# SCH_SUB_BUTTON.net
KiCad netlist of a schematic drawn in Altium Designer
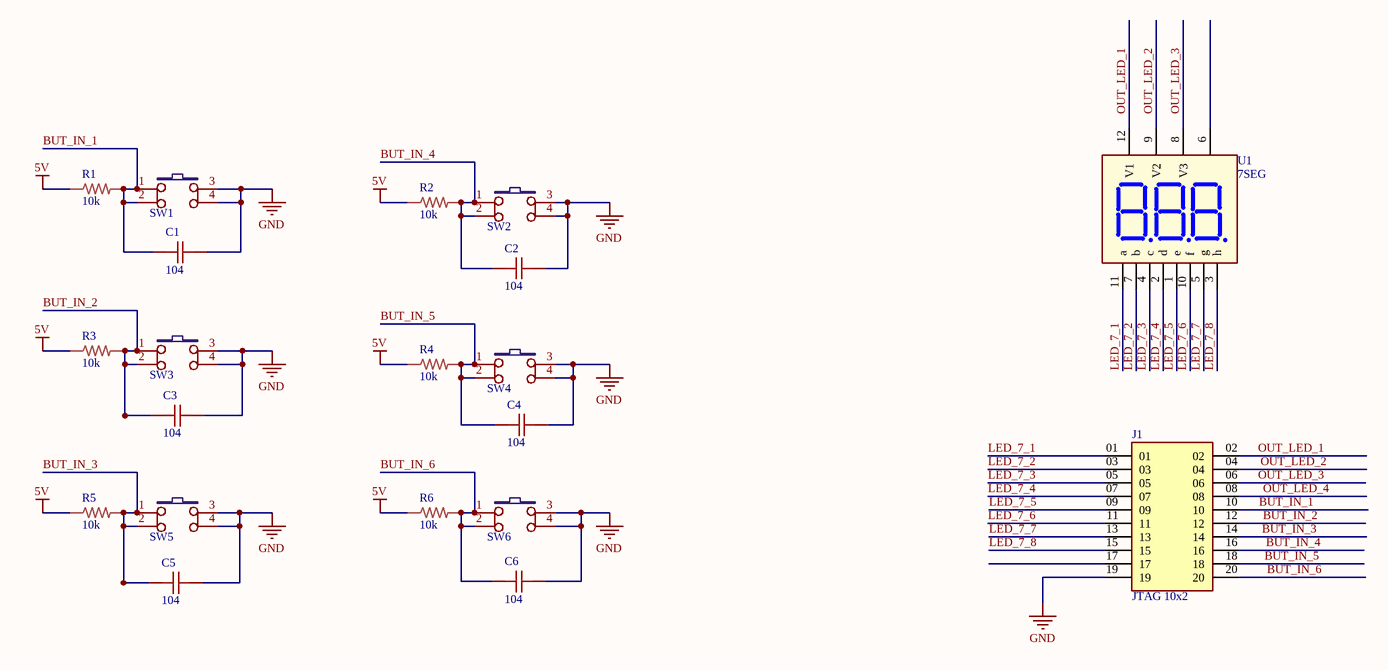
[diagram p0: SCH_SUB_BUTTON.SchDoc]

(export (version "E")
  (design (tool "Eeschema 10.0.6"))
  (components
    (comp (ref "C1")
      (value "104")
      (footprint "CAP_SMD_1206")
      (description "Cap SMD multiple types as 0402 0603 0805 1206")
      (fields (field (name "Comment") "Cap_SMD"))
      (libsource (lib "Integrated_Library_Kylin915") (part "Cap_SMD"))
    )
    (comp (ref "C2")
      (value "104")
      (footprint "CAP_SMD_1206")
      (description "Cap SMD multiple types as 0402 0603 0805 1206")
      (fields (field (name "Comment") "Cap_SMD"))
      (libsource (lib "Integrated_Library_Kylin915") (part "Cap_SMD"))
    )
    (comp (ref "C3")
      (value "104")
      (footprint "CAP_SMD_1206")
      (description "Cap SMD multiple types as 0402 0603 0805 1206")
      (fields (field (name "Comment") "Cap_SMD"))
      (libsource (lib "Integrated_Library_Kylin915") (part "Cap_SMD"))
    )
    (comp (ref "C4")
      (value "104")
      (footprint "CAP_SMD_1206")
      (description "Cap SMD multiple types as 0402 0603 0805 1206")
      (fields (field (name "Comment") "Cap_SMD"))
      (libsource (lib "Integrated_Library_Kylin915") (part "Cap_SMD"))
    )
    (comp (ref "C5")
      (value "104")
      (footprint "CAP_SMD_1206")
      (description "Cap SMD multiple types as 0402 0603 0805 1206")
      (fields (field (name "Comment") "Cap_SMD"))
      (libsource (lib "Integrated_Library_Kylin915") (part "Cap_SMD"))
    )
    (comp (ref "C6")
      (value "104")
      (footprint "CAP_SMD_1206")
      (description "Cap SMD multiple types as 0402 0603 0805 1206")
      (fields (field (name "Comment") "Cap_SMD"))
      (libsource (lib "Integrated_Library_Kylin915") (part "Cap_SMD"))
    )
    (comp (ref "J1")
      (value "JTAG 10x2")
      (footprint "JTAG")
      (description "Connector Header Through Hole 20 position 0.100 (2.54mm)")
      (fields (field (name "MP") "TSS-110-01-G-D") (field (name "MF") "Samtec"))
      (libsource (lib "library_principle_circuit_dang_nhien") (part "JTAG 10x2"))
    )
    (comp (ref "R1")
      (value "10k")
      (footprint "Res_SMD_1206")
      (description "res smd")
      (fields (field (name "Comment") "Res_SMD"))
      (libsource (lib "Integrated_Library_Kylin915") (part "Res_SMD"))
    )
    (comp (ref "R2")
      (value "10k")
      (footprint "Res_SMD_1206")
      (description "res smd")
      (fields (field (name "Comment") "Res_SMD"))
      (libsource (lib "Integrated_Library_Kylin915") (part "Res_SMD"))
    )
    (comp (ref "R3")
      (value "10k")
      (footprint "Res_SMD_1206")
      (description "res smd")
      (fields (field (name "Comment") "Res_SMD"))
      (libsource (lib "Integrated_Library_Kylin915") (part "Res_SMD"))
    )
    (comp (ref "R4")
      (value "10k")
      (footprint "Res_SMD_1206")
      (description "res smd")
      (fields (field (name "Comment") "Res_SMD"))
      (libsource (lib "Integrated_Library_Kylin915") (part "Res_SMD"))
    )
    (comp (ref "R5")
      (value "10k")
      (footprint "Res_SMD_1206")
      (description "res smd")
      (fields (field (name "Comment") "Res_SMD"))
      (libsource (lib "Integrated_Library_Kylin915") (part "Res_SMD"))
    )
    (comp (ref "R6")
      (value "10k")
      (footprint "Res_SMD_1206")
      (description "res smd")
      (fields (field (name "Comment") "Res_SMD"))
      (libsource (lib "Integrated_Library_Kylin915") (part "Res_SMD"))
    )
    (comp (ref "SW1")
      (value "Button6x6")
      (footprint "Button6x6smd")
      (description "button 6x6 mm")
      (libsource (lib "Integrated_Library_Kylin915") (part "Button6x6"))
    )
    (comp (ref "SW2")
      (value "Button6x6")
      (footprint "Button6x6smd")
      (description "button 6x6 mm")
      (libsource (lib "Integrated_Library_Kylin915") (part "Button6x6"))
    )
    (comp (ref "SW3")
      (value "Button6x6")
      (footprint "Button6x6smd")
      (description "button 6x6 mm")
      (libsource (lib "Integrated_Library_Kylin915") (part "Button6x6"))
    )
    (comp (ref "SW4")
      (value "Button6x6")
      (footprint "Button6x6smd")
      (description "button 6x6 mm")
      (libsource (lib "Integrated_Library_Kylin915") (part "Button6x6"))
    )
    (comp (ref "SW5")
      (value "Button6x6")
      (footprint "Button6x6smd")
      (description "button 6x6 mm")
      (libsource (lib "Integrated_Library_Kylin915") (part "Button6x6"))
    )
    (comp (ref "SW6")
      (value "Button6x6")
      (footprint "Button6x6smd")
      (description "button 6x6 mm")
      (libsource (lib "Integrated_Library_Kylin915") (part "Button6x6"))
    )
    (comp (ref "U1")
      (value "7SEG")
      (footprint "7SEG")
      (description "Three 7 Seg Dipslay")
      (libsource (lib "Integrated_Library_Kylin915") (part "LED 7SEG"))
    )
  )
  (nets
    (net (code "1") (name "/BUT_IN_1") (class "Default")
      (node (ref "C1") (pin "2") (pinfunction "2_2") (pintype "passive"))
      (node (ref "J1") (pin "10") (pinfunction "10_10") (pintype "passive"))
      (node (ref "R1") (pin "2") (pinfunction "2_2") (pintype "passive"))
      (node (ref "SW1") (pin "1") (pinfunction "1_1") (pintype "passive"))
      (node (ref "SW1") (pin "2") (pinfunction "2_2") (pintype "passive"))
    )
    (net (code "2") (name "/BUT_IN_2") (class "Default")
      (node (ref "C3") (pin "2") (pinfunction "2_2") (pintype "passive"))
      (node (ref "J1") (pin "12") (pinfunction "12_12") (pintype "passive"))
      (node (ref "R3") (pin "2") (pinfunction "2_2") (pintype "passive"))
      (node (ref "SW3") (pin "1") (pinfunction "1_1") (pintype "passive"))
      (node (ref "SW3") (pin "2") (pinfunction "2_2") (pintype "passive"))
    )
    (net (code "3") (name "/BUT_IN_3") (class "Default")
      (node (ref "C5") (pin "2") (pinfunction "2_2") (pintype "passive"))
      (node (ref "J1") (pin "14") (pinfunction "14_14") (pintype "passive"))
      (node (ref "R5") (pin "2") (pinfunction "2_2") (pintype "passive"))
      (node (ref "SW5") (pin "1") (pinfunction "1_1") (pintype "passive"))
      (node (ref "SW5") (pin "2") (pinfunction "2_2") (pintype "passive"))
    )
    (net (code "4") (name "/BUT_IN_4") (class "Default")
      (node (ref "C2") (pin "2") (pinfunction "2_2") (pintype "passive"))
      (node (ref "J1") (pin "16") (pinfunction "16_16") (pintype "passive"))
      (node (ref "R2") (pin "2") (pinfunction "2_2") (pintype "passive"))
      (node (ref "SW2") (pin "1") (pinfunction "1_1") (pintype "passive"))
      (node (ref "SW2") (pin "2") (pinfunction "2_2") (pintype "passive"))
    )
    (net (code "5") (name "/BUT_IN_5") (class "Default")
      (node (ref "C4") (pin "2") (pinfunction "2_2") (pintype "passive"))
      (node (ref "J1") (pin "18") (pinfunction "18_18") (pintype "passive"))
      (node (ref "R4") (pin "2") (pinfunction "2_2") (pintype "passive"))
      (node (ref "SW4") (pin "1") (pinfunction "1_1") (pintype "passive"))
      (node (ref "SW4") (pin "2") (pinfunction "2_2") (pintype "passive"))
    )
    (net (code "6") (name "/BUT_IN_6") (class "Default")
      (node (ref "C6") (pin "2") (pinfunction "2_2") (pintype "passive"))
      (node (ref "J1") (pin "20") (pinfunction "20_20") (pintype "passive"))
      (node (ref "R6") (pin "2") (pinfunction "2_2") (pintype "passive"))
      (node (ref "SW6") (pin "1") (pinfunction "1_1") (pintype "passive"))
      (node (ref "SW6") (pin "2") (pinfunction "2_2") (pintype "passive"))
    )
    (net (code "7") (name "/LED_7_1") (class "Default")
      (node (ref "J1") (pin "01") (pinfunction "01_01") (pintype "passive"))
      (node (ref "U1") (pin "11") (pinfunction "a_11") (pintype "passive"))
    )
    (net (code "8") (name "/LED_7_2") (class "Default")
      (node (ref "J1") (pin "03") (pinfunction "03_03") (pintype "passive"))
      (node (ref "U1") (pin "7") (pinfunction "b_7") (pintype "passive"))
    )
    (net (code "9") (name "/LED_7_3") (class "Default")
      (node (ref "J1") (pin "05") (pinfunction "05_05") (pintype "passive"))
      (node (ref "U1") (pin "4") (pinfunction "c_4") (pintype "passive"))
    )
    (net (code "10") (name "/LED_7_4") (class "Default")
      (node (ref "J1") (pin "07") (pinfunction "07_07") (pintype "passive"))
      (node (ref "U1") (pin "2") (pinfunction "d_2") (pintype "passive"))
    )
    (net (code "11") (name "/LED_7_5") (class "Default")
      (node (ref "J1") (pin "09") (pinfunction "09_09") (pintype "passive"))
      (node (ref "U1") (pin "1") (pinfunction "e_1") (pintype "passive"))
    )
    (net (code "12") (name "/LED_7_6") (class "Default")
      (node (ref "J1") (pin "11") (pinfunction "11_11") (pintype "passive"))
      (node (ref "U1") (pin "10") (pinfunction "f_10") (pintype "passive"))
    )
    (net (code "13") (name "/LED_7_7") (class "Default")
      (node (ref "J1") (pin "13") (pinfunction "13_13") (pintype "passive"))
      (node (ref "U1") (pin "5") (pinfunction "g_5") (pintype "passive"))
    )
    (net (code "14") (name "/LED_7_8") (class "Default")
      (node (ref "J1") (pin "15") (pinfunction "15_15") (pintype "passive"))
      (node (ref "U1") (pin "3") (pinfunction "h_3") (pintype "passive"))
    )
    (net (code "15") (name "/OUT_LED_1") (class "Default")
      (node (ref "J1") (pin "02") (pinfunction "02_02") (pintype "passive"))
      (node (ref "U1") (pin "12") (pinfunction "V1_12") (pintype "passive"))
    )
    (net (code "16") (name "/OUT_LED_2") (class "Default")
      (node (ref "J1") (pin "04") (pinfunction "04_04") (pintype "passive"))
      (node (ref "U1") (pin "9") (pinfunction "V2_9") (pintype "passive"))
    )
    (net (code "17") (name "/OUT_LED_3") (class "Default")
      (node (ref "J1") (pin "06") (pinfunction "06_06") (pintype "passive"))
      (node (ref "U1") (pin "8") (pinfunction "V3_8") (pintype "passive"))
    )
    (net (code "18") (name "/OUT_LED_4") (class "Default")
      (node (ref "J1") (pin "08") (pinfunction "08_08") (pintype "passive"))
    )
    (net (code "19") (name "5V") (class "Default")
      (node (ref "R1") (pin "1") (pinfunction "1_1") (pintype "passive"))
      (node (ref "R2") (pin "1") (pinfunction "1_1") (pintype "passive"))
      (node (ref "R3") (pin "1") (pinfunction "1_1") (pintype "passive"))
      (node (ref "R4") (pin "1") (pinfunction "1_1") (pintype "passive"))
      (node (ref "R5") (pin "1") (pinfunction "1_1") (pintype "passive"))
      (node (ref "R6") (pin "1") (pinfunction "1_1") (pintype "passive"))
    )
    (net (code "20") (name "GND") (class "Default")
      (node (ref "C1") (pin "1") (pinfunction "1_1") (pintype "passive"))
      (node (ref "C2") (pin "1") (pinfunction "1_1") (pintype "passive"))
      (node (ref "C3") (pin "1") (pinfunction "1_1") (pintype "passive"))
      (node (ref "C4") (pin "1") (pinfunction "1_1") (pintype "passive"))
      (node (ref "C5") (pin "1") (pinfunction "1_1") (pintype "passive"))
      (node (ref "C6") (pin "1") (pinfunction "1_1") (pintype "passive"))
      (node (ref "J1") (pin "19") (pinfunction "19_19") (pintype "passive"))
      (node (ref "SW1") (pin "3") (pinfunction "3_3") (pintype "passive"))
      (node (ref "SW1") (pin "4") (pinfunction "4_4") (pintype "passive"))
      (node (ref "SW2") (pin "3") (pinfunction "3_3") (pintype "passive"))
      (node (ref "SW2") (pin "4") (pinfunction "4_4") (pintype "passive"))
      (node (ref "SW3") (pin "3") (pinfunction "3_3") (pintype "passive"))
      (node (ref "SW3") (pin "4") (pinfunction "4_4") (pintype "passive"))
      (node (ref "SW4") (pin "3") (pinfunction "3_3") (pintype "passive"))
      (node (ref "SW4") (pin "4") (pinfunction "4_4") (pintype "passive"))
      (node (ref "SW5") (pin "3") (pinfunction "3_3") (pintype "passive"))
      (node (ref "SW5") (pin "4") (pinfunction "4_4") (pintype "passive"))
      (node (ref "SW6") (pin "3") (pinfunction "3_3") (pintype "passive"))
      (node (ref "SW6") (pin "4") (pinfunction "4_4") (pintype "passive"))
    )
    (net (code "21") (name "unconnected-(J1-Pad17)") (class "Default")
      (node (ref "J1") (pin "17") (pinfunction "17_17") (pintype "passive"))
    )
    (net (code "22") (name "unconnected-(U1-V4-Pad6)") (class "Default")
      (node (ref "U1") (pin "6") (pinfunction "V4_6") (pintype "passive"))
    )
  )
)
